# MultiStage_Cascade_SOT343.net
KiCad netlist of a schematic drawn in Altium Designer
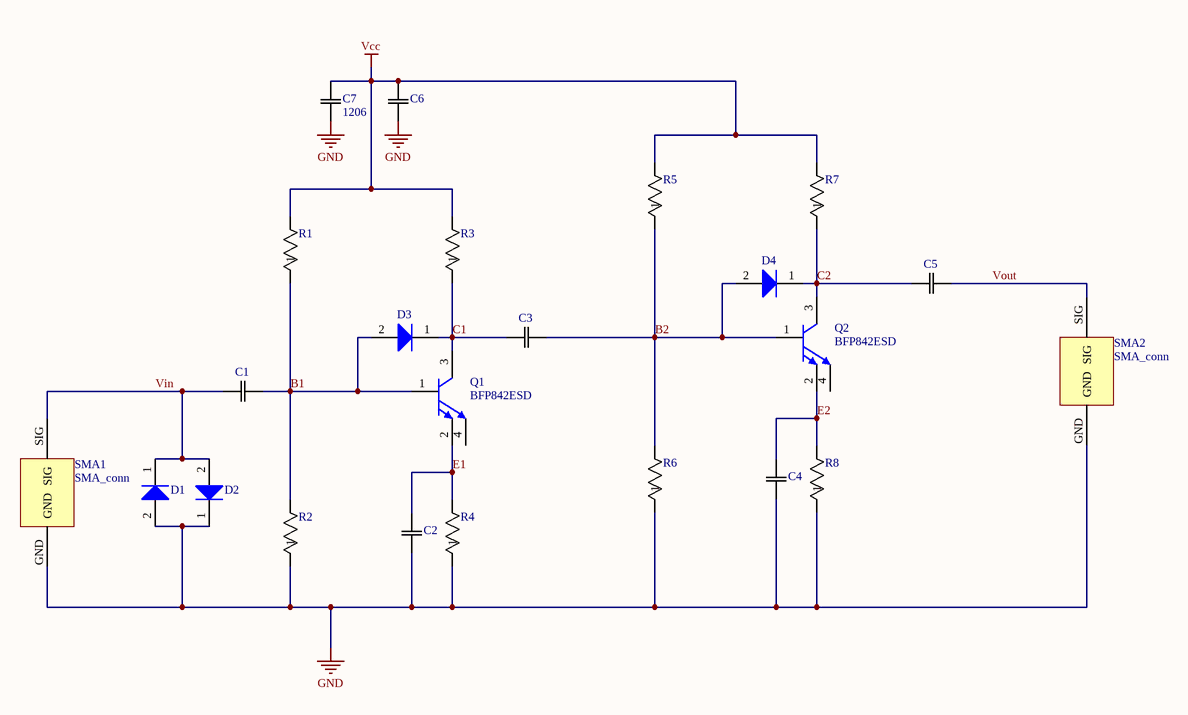
[diagram p0: MultiStage_Cascade_SOT343.SchDoc]

(export (version "E")
  (design (tool "Eeschema 10.0.6"))
  (components
    (comp (ref "C1")
      (value "~")
      (footprint "CAP_K1")
      (description "No Description Available")
      (fields
        (field (name "MANUFACTURER_PART_NUMBER") "ECH-U1C182GX5")
        (field (name "COPYRIGHT") "Copyright (C) 2018 Accelerated Designs. All rights reserved")
      )
      (libsource (lib "0603Capacitor") (part "ECH-U1C182GX5"))
    )
    (comp (ref "C2")
      (value "~")
      (footprint "CAP_K1")
      (description "No Description Available")
      (fields
        (field (name "MANUFACTURER_PART_NUMBER") "ECH-U1C182GX5")
        (field (name "COPYRIGHT") "Copyright (C) 2018 Accelerated Designs. All rights reserved")
      )
      (libsource (lib "0603Capacitor") (part "ECH-U1C182GX5"))
    )
    (comp (ref "C3")
      (value "~")
      (footprint "CAP_K1")
      (description "No Description Available")
      (fields
        (field (name "MANUFACTURER_PART_NUMBER") "ECH-U1C182GX5")
        (field (name "COPYRIGHT") "Copyright (C) 2018 Accelerated Designs. All rights reserved")
      )
      (libsource (lib "0603Capacitor") (part "ECH-U1C182GX5"))
    )
    (comp (ref "C4")
      (value "~")
      (footprint "CAP_K1")
      (description "No Description Available")
      (fields
        (field (name "MANUFACTURER_PART_NUMBER") "ECH-U1C182GX5")
        (field (name "COPYRIGHT") "Copyright (C) 2018 Accelerated Designs. All rights reserved")
      )
      (libsource (lib "0603Capacitor") (part "ECH-U1C182GX5"))
    )
    (comp (ref "C5")
      (value "~")
      (footprint "CAP_K1")
      (description "No Description Available")
      (fields
        (field (name "MANUFACTURER_PART_NUMBER") "ECH-U1C182GX5")
        (field (name "COPYRIGHT") "Copyright (C) 2018 Accelerated Designs. All rights reserved")
      )
      (libsource (lib "0603Capacitor") (part "ECH-U1C182GX5"))
    )
    (comp (ref "C6")
      (value "~")
      (footprint "CAP_K1")
      (description "No Description Available")
      (fields
        (field (name "MANUFACTURER_PART_NUMBER") "ECH-U1C182GX5")
        (field (name "COPYRIGHT") "Copyright (C) 2018 Accelerated Designs. All rights reserved")
      )
      (libsource (lib "0603Capacitor") (part "ECH-U1C182GX5"))
    )
    (comp (ref "C7")
      (value "1206")
      (footprint "C1206C")
      (description "No Description Available")
      (fields
        (field (name "MANUFACTURER_PART_NUMBER") "C1206C221KDGACTU")
        (field (name "COPYRIGHT") "Copyright (C) 2018 Accelerated Designs. All rights reserved")
      )
      (libsource (lib "1206Capacitor") (part "C1206C221KDGACTU"))
    )
    (comp (ref "D1")
      (value "~")
      (footprint "INF-SOD323_V")
      (description "Single Silicon Schottky Diode, 110 mA IF Max, SOD32, Green")
      (fields (field (name "MANUFACTURER") "Infineon") (field (name "PARTNUMBER") "BAT15-03W"))
      (libsource (lib "Infineon_RFSchottkyDiode_SOD323") (part "BAT15-03W"))
    )
    (comp (ref "D2")
      (value "~")
      (footprint "INF-SOD323_V")
      (description "Single Silicon Schottky Diode, 110 mA IF Max, SOD32, Green")
      (fields (field (name "MANUFACTURER") "Infineon") (field (name "PARTNUMBER") "BAT15-03W"))
      (libsource (lib "Infineon_RFSchottkyDiode_SOD323") (part "BAT15-03W"))
    )
    (comp (ref "D3")
      (value "~")
      (footprint "INF-SOD323_V")
      (description "Single Silicon Schottky Diode, 110 mA IF Max, SOD32, Green")
      (fields (field (name "MANUFACTURER") "Infineon") (field (name "PARTNUMBER") "BAT15-03W"))
      (libsource (lib "Infineon_RFSchottkyDiode_SOD323") (part "BAT15-03W"))
    )
    (comp (ref "D4")
      (value "~")
      (footprint "INF-SOD323_V")
      (description "Single Silicon Schottky Diode, 110 mA IF Max, SOD32, Green")
      (fields (field (name "MANUFACTURER") "Infineon") (field (name "PARTNUMBER") "BAT15-03W"))
      (libsource (lib "Infineon_RFSchottkyDiode_SOD323") (part "BAT15-03W"))
    )
    (comp (ref "Q1")
      (value "BFP842ESD")
      (footprint "INF-SOT343_V")
      (fields (field (name "MANUFACTURER") "Infineon"))
      (libsource (lib "Infineon_RFBJT_SOT343") (part "BFP842ESD"))
    )
    (comp (ref "Q2")
      (value "BFP842ESD")
      (footprint "INF-SOT343_V")
      (fields (field (name "MANUFACTURER") "Infineon"))
      (libsource (lib "Infineon_RFBJT_SOT343") (part "BFP842ESD"))
    )
    (comp (ref "R1")
      (value "~")
      (footprint "RES_RC0201_P6XP3")
      (description "No Description Available")
      (fields
        (field (name "MANUFACTURER_PART_NUMBER") "RC0201FR-0718KL")
        (field (name "COPYRIGHT") "Copyright (C) 2018 Accelerated Designs. All rights reserved")
      )
      (libsource (lib "0201Resistor_Yageo") (part "RC0201FR-0718KL"))
    )
    (comp (ref "R2")
      (value "~")
      (footprint "RES_RC0201_P6XP3")
      (description "No Description Available")
      (fields
        (field (name "MANUFACTURER_PART_NUMBER") "RC0201FR-0718KL")
        (field (name "COPYRIGHT") "Copyright (C) 2018 Accelerated Designs. All rights reserved")
      )
      (libsource (lib "0201Resistor_Yageo") (part "RC0201FR-0718KL"))
    )
    (comp (ref "R3")
      (value "~")
      (footprint "RES_RC0201_P6XP3")
      (description "No Description Available")
      (fields
        (field (name "MANUFACTURER_PART_NUMBER") "RC0201FR-0718KL")
        (field (name "COPYRIGHT") "Copyright (C) 2018 Accelerated Designs. All rights reserved")
      )
      (libsource (lib "0201Resistor_Yageo") (part "RC0201FR-0718KL"))
    )
    (comp (ref "R4")
      (value "~")
      (footprint "RES_RC0201_P6XP3")
      (description "No Description Available")
      (fields
        (field (name "MANUFACTURER_PART_NUMBER") "RC0201FR-0718KL")
        (field (name "COPYRIGHT") "Copyright (C) 2018 Accelerated Designs. All rights reserved")
      )
      (libsource (lib "0201Resistor_Yageo") (part "RC0201FR-0718KL"))
    )
    (comp (ref "R5")
      (value "~")
      (footprint "RES_RC0201_P6XP3")
      (description "No Description Available")
      (fields
        (field (name "MANUFACTURER_PART_NUMBER") "RC0201FR-0718KL")
        (field (name "COPYRIGHT") "Copyright (C) 2018 Accelerated Designs. All rights reserved")
      )
      (libsource (lib "0201Resistor_Yageo") (part "RC0201FR-0718KL"))
    )
    (comp (ref "R6")
      (value "~")
      (footprint "RES_RC0201_P6XP3")
      (description "No Description Available")
      (fields
        (field (name "MANUFACTURER_PART_NUMBER") "RC0201FR-0718KL")
        (field (name "COPYRIGHT") "Copyright (C) 2018 Accelerated Designs. All rights reserved")
      )
      (libsource (lib "0201Resistor_Yageo") (part "RC0201FR-0718KL"))
    )
    (comp (ref "R7")
      (value "~")
      (footprint "RES_RC0201_P6XP3")
      (description "No Description Available")
      (fields
        (field (name "MANUFACTURER_PART_NUMBER") "RC0201FR-0718KL")
        (field (name "COPYRIGHT") "Copyright (C) 2018 Accelerated Designs. All rights reserved")
      )
      (libsource (lib "0201Resistor_Yageo") (part "RC0201FR-0718KL"))
    )
    (comp (ref "R8")
      (value "~")
      (footprint "RES_RC0201_P6XP3")
      (description "No Description Available")
      (fields
        (field (name "MANUFACTURER_PART_NUMBER") "RC0201FR-0718KL")
        (field (name "COPYRIGHT") "Copyright (C) 2018 Accelerated Designs. All rights reserved")
      )
      (libsource (lib "0201Resistor_Yageo") (part "RC0201FR-0718KL"))
    )
    (comp (ref "SMA1")
      (value "SMA_conn")
      (footprint "SMA_conn")
      (libsource (lib "SMA_conn") (part "SMA_conn"))
    )
    (comp (ref "SMA2")
      (value "SMA_conn")
      (footprint "SMA_conn")
      (libsource (lib "SMA_conn") (part "SMA_conn"))
    )
  )
  (nets
    (net (code "1") (name "/B1") (class "Default")
      (node (ref "C1") (pin "2") (pinfunction "2_2") (pintype "passive"))
      (node (ref "D3") (pin "2") (pinfunction "A_2") (pintype "passive"))
      (node (ref "Q1") (pin "1") (pinfunction "B_1") (pintype "passive"))
      (node (ref "R1") (pin "1") (pinfunction "1_1") (pintype "passive"))
      (node (ref "R2") (pin "2") (pinfunction "2_2") (pintype "passive"))
    )
    (net (code "2") (name "/B2") (class "Default")
      (node (ref "C3") (pin "1") (pinfunction "1_1") (pintype "passive"))
      (node (ref "D4") (pin "2") (pinfunction "A_2") (pintype "passive"))
      (node (ref "Q2") (pin "1") (pinfunction "B_1") (pintype "passive"))
      (node (ref "R5") (pin "1") (pinfunction "1_1") (pintype "passive"))
      (node (ref "R6") (pin "2") (pinfunction "2_2") (pintype "passive"))
    )
    (net (code "3") (name "/C1") (class "Default")
      (node (ref "C3") (pin "2") (pinfunction "2_2") (pintype "passive"))
      (node (ref "D3") (pin "1") (pinfunction "K_1") (pintype "passive"))
      (node (ref "Q1") (pin "3") (pinfunction "C_3") (pintype "passive"))
      (node (ref "R3") (pin "1") (pinfunction "1_1") (pintype "passive"))
    )
    (net (code "4") (name "/C2") (class "Default")
      (node (ref "C5") (pin "2") (pinfunction "2_2") (pintype "passive"))
      (node (ref "D4") (pin "1") (pinfunction "K_1") (pintype "passive"))
      (node (ref "Q2") (pin "3") (pinfunction "C_3") (pintype "passive"))
      (node (ref "R7") (pin "1") (pinfunction "1_1") (pintype "passive"))
    )
    (net (code "5") (name "/E1") (class "Default")
      (node (ref "C2") (pin "2") (pinfunction "2_2") (pintype "passive"))
      (node (ref "Q1") (pin "2") (pinfunction "E_2") (pintype "passive"))
      (node (ref "R4") (pin "2") (pinfunction "2_2") (pintype "passive"))
    )
    (net (code "6") (name "/E2") (class "Default")
      (node (ref "C4") (pin "2") (pinfunction "2_2") (pintype "passive"))
      (node (ref "Q2") (pin "2") (pinfunction "E_2") (pintype "passive"))
      (node (ref "R8") (pin "2") (pinfunction "2_2") (pintype "passive"))
    )
    (net (code "7") (name "/Vin") (class "Default")
      (node (ref "C1") (pin "1") (pinfunction "1_1") (pintype "passive"))
      (node (ref "D1") (pin "1") (pinfunction "K_1") (pintype "passive"))
      (node (ref "D2") (pin "2") (pinfunction "A_2") (pintype "passive"))
      (node (ref "SMA1") (pin "SIG") (pinfunction "SIG_SIG") (pintype "passive"))
    )
    (net (code "8") (name "/Vout") (class "Default")
      (node (ref "C5") (pin "1") (pinfunction "1_1") (pintype "passive"))
      (node (ref "SMA2") (pin "SIG") (pinfunction "SIG_SIG") (pintype "passive"))
    )
    (net (code "9") (name "GND") (class "Default")
      (node (ref "C2") (pin "1") (pinfunction "1_1") (pintype "passive"))
      (node (ref "C4") (pin "1") (pinfunction "1_1") (pintype "passive"))
      (node (ref "C6") (pin "1") (pinfunction "1_1") (pintype "passive"))
      (node (ref "C7") (pin "1") (pinfunction "1_1") (pintype "passive"))
      (node (ref "D1") (pin "2") (pinfunction "A_2") (pintype "passive"))
      (node (ref "D2") (pin "1") (pinfunction "K_1") (pintype "passive"))
      (node (ref "R2") (pin "1") (pinfunction "1_1") (pintype "passive"))
      (node (ref "R4") (pin "1") (pinfunction "1_1") (pintype "passive"))
      (node (ref "R6") (pin "1") (pinfunction "1_1") (pintype "passive"))
      (node (ref "R8") (pin "1") (pinfunction "1_1") (pintype "passive"))
      (node (ref "SMA1") (pin "GND") (pinfunction "GND_GND") (pintype "passive"))
      (node (ref "SMA2") (pin "GND") (pinfunction "GND_GND") (pintype "passive"))
    )
    (net (code "10") (name "Vcc") (class "Default")
      (node (ref "C6") (pin "2") (pinfunction "2_2") (pintype "passive"))
      (node (ref "C7") (pin "2") (pinfunction "2_2") (pintype "passive"))
      (node (ref "R1") (pin "2") (pinfunction "2_2") (pintype "passive"))
      (node (ref "R3") (pin "2") (pinfunction "2_2") (pintype "passive"))
      (node (ref "R5") (pin "2") (pinfunction "2_2") (pintype "passive"))
      (node (ref "R7") (pin "2") (pinfunction "2_2") (pintype "passive"))
    )
    (net (code "11") (name "unconnected-(Q1-E-Pad4)") (class "Default")
      (node (ref "Q1") (pin "4") (pinfunction "E_4") (pintype "passive"))
    )
    (net (code "12") (name "unconnected-(Q2-E-Pad4)") (class "Default")
      (node (ref "Q2") (pin "4") (pinfunction "E_4") (pintype "passive"))
    )
  )
)
